# EVGP_Daugherboard_2.net
KiCad netlist of a schematic drawn in EAGLE
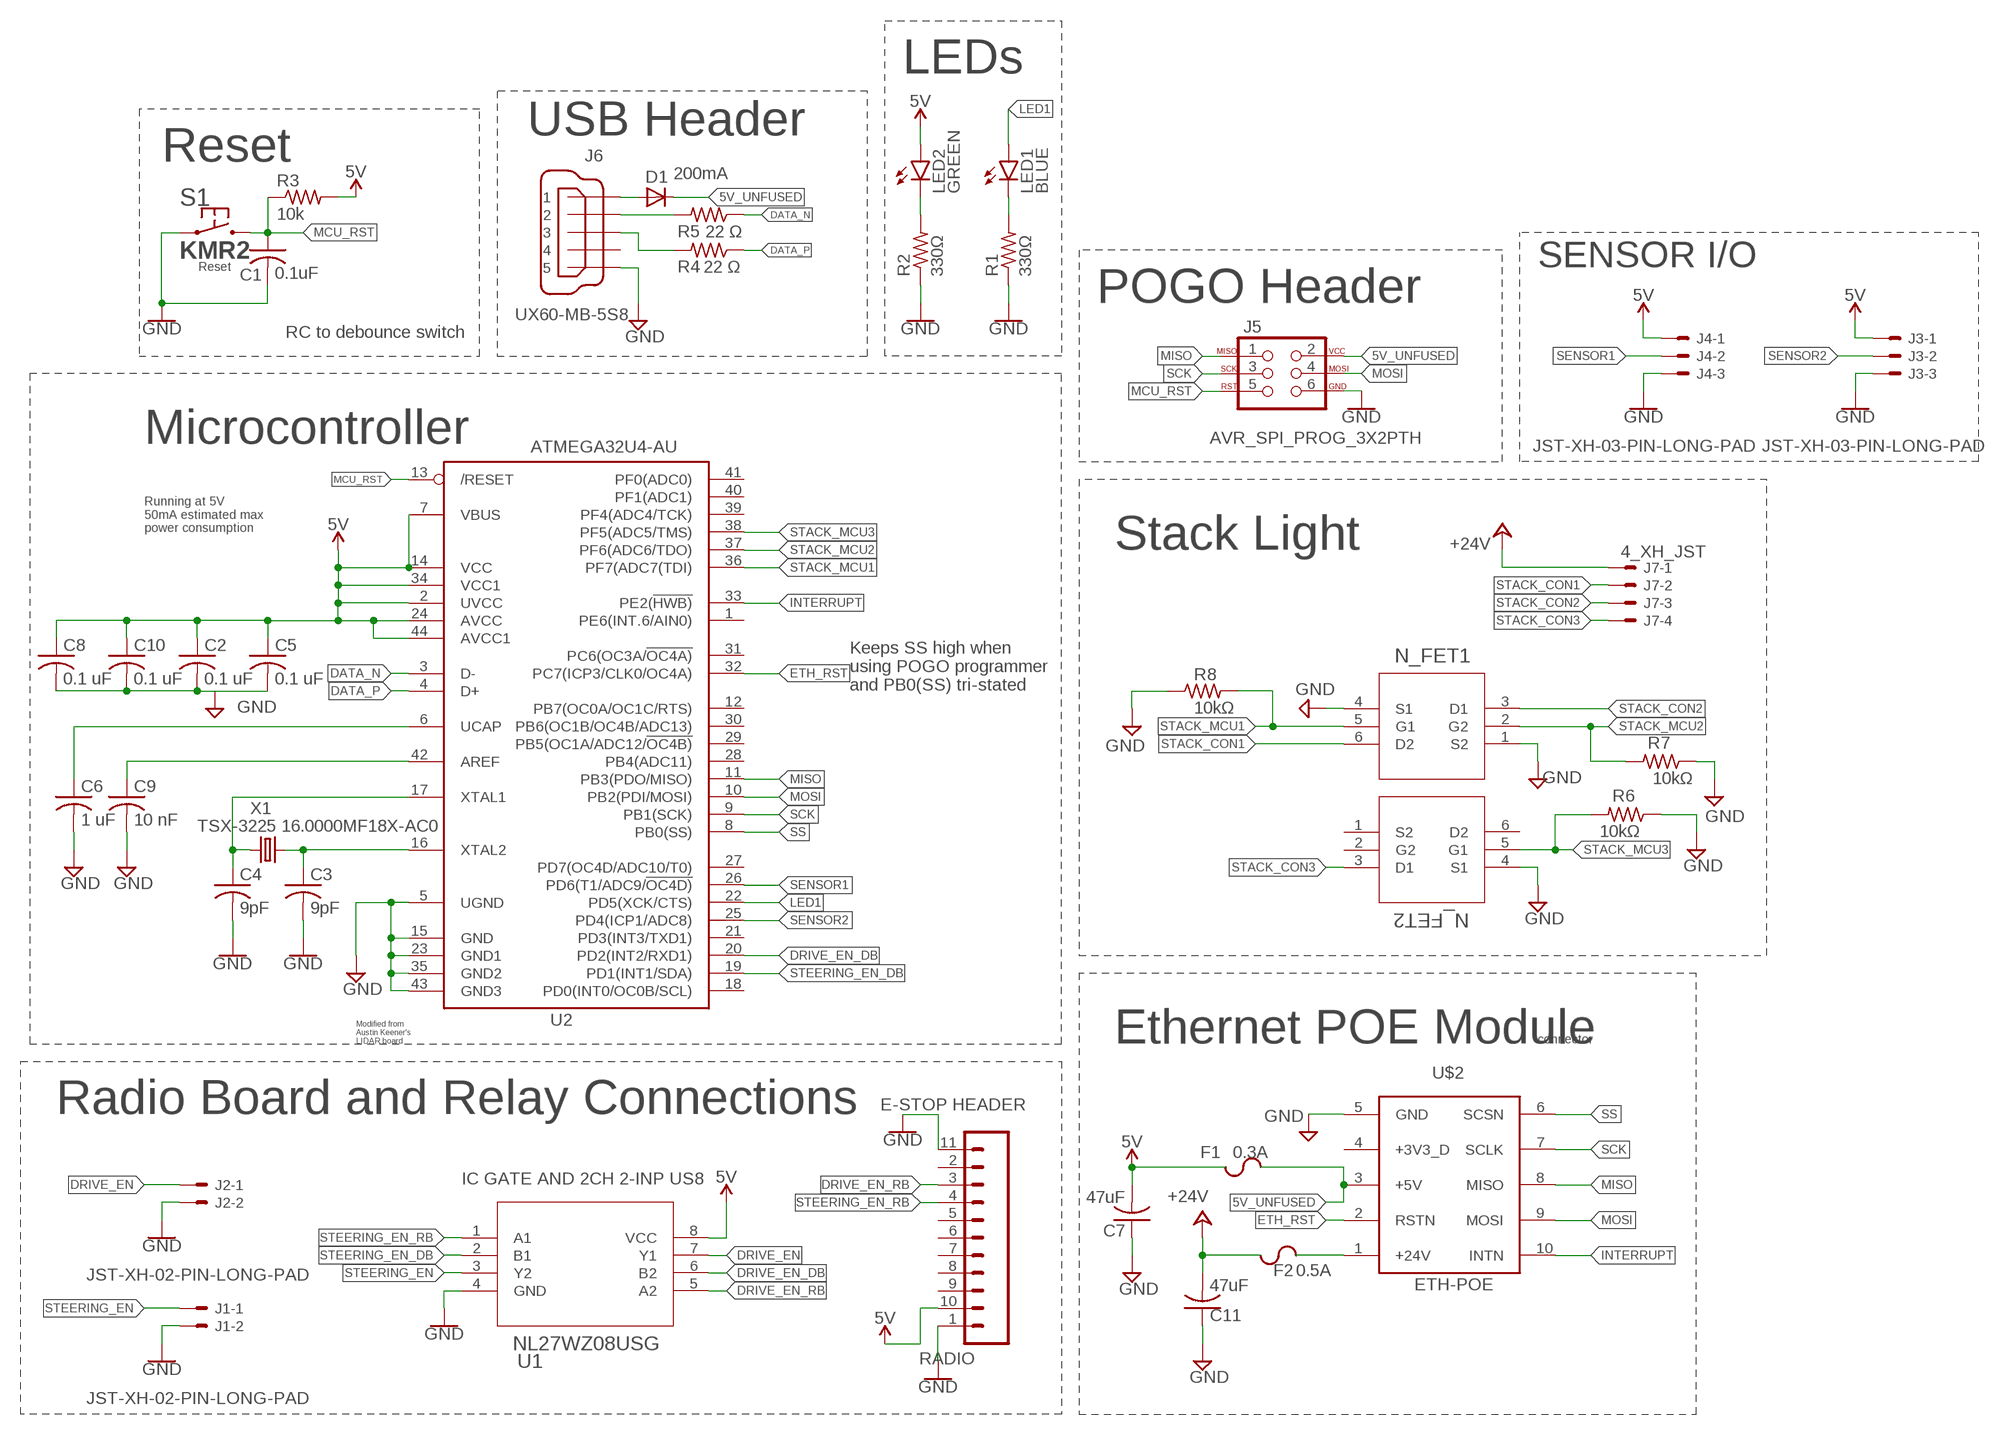
[diagram p0: schematic, sheet 1]

(export (version "E")
  (design (tool "Eeschema 10.0.6"))
  (components
    (comp (ref "C1")
      (value "0.1uF")
      (footprint "eagle-import:C0603")
      (libsource (lib "eagle-import") (part "C-USC0603"))
    )
    (comp (ref "C2")
      (value "0.1 uF")
      (footprint "eagle-import:C0603")
      (libsource (lib "eagle-import") (part "resistor_348_C-USC0603"))
    )
    (comp (ref "C3")
      (value "9pF")
      (footprint "eagle-import:C0603")
      (libsource (lib "eagle-import") (part "resistor_348_C-USC0603"))
    )
    (comp (ref "C4")
      (value "9pF")
      (footprint "eagle-import:C0603")
      (libsource (lib "eagle-import") (part "resistor_348_C-USC0603"))
    )
    (comp (ref "C5")
      (value "0.1 uF")
      (footprint "eagle-import:C0603")
      (libsource (lib "eagle-import") (part "resistor_348_C-USC0603"))
    )
    (comp (ref "C6")
      (value "1 uF")
      (footprint "eagle-import:C0603")
      (libsource (lib "eagle-import") (part "resistor_348_C-USC0603"))
    )
    (comp (ref "C7")
      (value "47uF")
      (footprint "eagle-import:C1206")
      (libsource (lib "eagle-import") (part "C-USC1206"))
    )
    (comp (ref "C8")
      (value "0.1 uF")
      (footprint "eagle-import:C0603")
      (libsource (lib "eagle-import") (part "resistor_348_C-USC0603"))
    )
    (comp (ref "C9")
      (value "10 nF")
      (footprint "eagle-import:C0603")
      (libsource (lib "eagle-import") (part "resistor_348_C-USC0603"))
    )
    (comp (ref "C10")
      (value "0.1 uF")
      (footprint "eagle-import:C0603")
      (libsource (lib "eagle-import") (part "resistor_348_C-USC0603"))
    )
    (comp (ref "C11")
      (value "47uF")
      (footprint "eagle-import:C1206")
      (libsource (lib "eagle-import") (part "C-USC1206"))
    )
    (comp (ref "D1")
      (value "200mA")
      (footprint "eagle-import:SOD323-R")
      (libsource (lib "eagle-import") (part "DIODE-SOD323-R"))
    )
    (comp (ref "F1")
      (value "0.3A")
      (footprint "eagle-import:F1206")
      (libsource (lib "eagle-import") (part "CHIP_FUSE1206"))
    )
    (comp (ref "F2")
      (value "0.5A")
      (footprint "eagle-import:F1206")
      (libsource (lib "eagle-import") (part "CHIP_FUSE1206"))
    )
    (comp (ref "J1")
      (value "JST-XH-02-PIN-LONG-PAD")
      (footprint "eagle-import:JST-XH-02-PACKAGE-LONG-PAD")
      (libsource (lib "eagle-import") (part "JST-XH-02-PIN-LONG-PAD"))
    )
    (comp (ref "J2")
      (value "JST-XH-02-PIN-LONG-PAD")
      (footprint "eagle-import:JST-XH-02-PACKAGE-LONG-PAD")
      (libsource (lib "eagle-import") (part "JST-XH-02-PIN-LONG-PAD"))
    )
    (comp (ref "J3")
      (value "JST-XH-03-PIN-LONG-PAD")
      (footprint "eagle-import:JST-XH-03-PACKAGE-LONG-PAD")
      (libsource (lib "eagle-import") (part "JST-XH-03-PIN-LONG-PAD"))
    )
    (comp (ref "J4")
      (value "JST-XH-03-PIN-LONG-PAD")
      (footprint "eagle-import:JST-XH-03-PACKAGE-LONG-PAD")
      (libsource (lib "eagle-import") (part "JST-XH-03-PIN-LONG-PAD"))
    )
    (comp (ref "J5")
      (value "AVR_SPI_PROG_3X2PTH")
      (footprint "eagle-import:2X3")
      (libsource (lib "eagle-import") (part "AVR_SPI_PROG_3X2PTH"))
    )
    (comp (ref "J6")
      (value "UX60-MB-5S8")
      (footprint "eagle-import:UX60-MB-5S8")
      (libsource (lib "eagle-import") (part "UX60-MB-5S?8"))
    )
    (comp (ref "J7")
      (value "4_XH_JST")
      (footprint "eagle-import:JST-XH-04-PACKAGE-LONG-PAD")
      (libsource (lib "eagle-import") (part "JST-XH-04-PIN-LONG-PAD"))
    )
    (comp (ref "LED1")
      (value "BLUE")
      (footprint "eagle-import:CHIP-LED0603")
      (libsource (lib "eagle-import") (part "LEDCHIP-LED0603"))
    )
    (comp (ref "LED2")
      (value "GREEN")
      (footprint "eagle-import:CHIP-LED0603")
      (libsource (lib "eagle-import") (part "LEDCHIP-LED0603"))
    )
    (comp (ref "Q1")
      (value "N_FET2")
      (footprint "eagle-import:SOT-363")
      (fields (field (name "MANUFACTURER_PART_NUMBER") "BSS84DW7F"))
      (libsource (lib "eagle-import") (part "BSS84DW-7-F"))
    )
    (comp (ref "Q2")
      (value "N_FET1")
      (footprint "eagle-import:SOT-363")
      (fields (field (name "MANUFACTURER_PART_NUMBER") "BSS84DW7F"))
      (libsource (lib "eagle-import") (part "BSS84DW-7-F"))
    )
    (comp (ref "R1")
      (value "330Ω")
      (footprint "eagle-import:R0603")
      (libsource (lib "eagle-import") (part "R-US_R0603"))
    )
    (comp (ref "R2")
      (value "330Ω")
      (footprint "eagle-import:R0603")
      (libsource (lib "eagle-import") (part "R-US_R0603"))
    )
    (comp (ref "R3")
      (value "10k")
      (footprint "eagle-import:R0603")
      (libsource (lib "eagle-import") (part "R-US_R0603"))
    )
    (comp (ref "R4")
      (value "22 Ω")
      (footprint "eagle-import:R0603")
      (libsource (lib "eagle-import") (part "R-US_R0603"))
    )
    (comp (ref "R5")
      (value "22 Ω")
      (footprint "eagle-import:R0603")
      (libsource (lib "eagle-import") (part "R-US_R0603"))
    )
    (comp (ref "R6")
      (value "10kΩ")
      (footprint "eagle-import:R0603")
      (libsource (lib "eagle-import") (part "R-US_R0603"))
    )
    (comp (ref "R7")
      (value "10kΩ")
      (footprint "eagle-import:R0603")
      (libsource (lib "eagle-import") (part "R-US_R0603"))
    )
    (comp (ref "R8")
      (value "10kΩ")
      (footprint "eagle-import:R0603")
      (libsource (lib "eagle-import") (part "R-US_R0603"))
    )
    (comp (ref "RADIO")
      (value "E-STOP HEADER")
      (footprint "eagle-import:RADIO_V1.3")
      (libsource (lib "eagle-import") (part "ESTOP_RADIO"))
    )
    (comp (ref "S1")
      (value "KMR2")
      (footprint "eagle-import:KMR2")
      (fields (field (name "FUNCTION") "Reset"))
      (libsource (lib "eagle-import") (part "KMR2"))
    )
    (comp (ref "U$2")
      (value "ETH-POE")
      (footprint "eagle-import:HDRVR10W64P4000X254_2X5_1016X508X254B")
      (libsource (lib "eagle-import") (part "ETH-POE"))
    )
    (comp (ref "U1")
      (value "NL27WZ08USG")
      (footprint "eagle-import:US8_2P40X2P10")
      (libsource (lib "eagle-import") (part "NL27WZ08USG"))
    )
    (comp (ref "U2")
      (value "ATMEGA32U4-AU")
      (footprint "eagle-import:TQFP44")
      (libsource (lib "eagle-import") (part "ATMEGA32U4-AU"))
    )
    (comp (ref "X1")
      (value "TSX-3225 16.0000MF18X-AC0")
      (footprint "eagle-import:XTAL-3.2X2.5")
      (libsource (lib "eagle-import") (part "XTAL-3.2X2.5"))
    )
  )
  (nets
    (net (code "1") (name "+24V") (class "Default")
      (node (ref "C11") (pin "2") (pinfunction "2_2") (pintype "passive"))
      (node (ref "F2") (pin "1") (pinfunction "1_1") (pintype "bidirectional"))
      (node (ref "J7") (pin "1") (pinfunction "S_1") (pintype "passive"))
    )
    (net (code "2") (name "5V") (class "Default")
      (node (ref "C10") (pin "1") (pinfunction "1_1") (pintype "passive"))
      (node (ref "C2") (pin "1") (pinfunction "1_1") (pintype "passive"))
      (node (ref "C5") (pin "1") (pinfunction "1_1") (pintype "passive"))
      (node (ref "C7") (pin "2") (pinfunction "2_2") (pintype "passive"))
      (node (ref "C8") (pin "1") (pinfunction "1_1") (pintype "passive"))
      (node (ref "F1") (pin "1") (pinfunction "1_1") (pintype "bidirectional"))
      (node (ref "J3") (pin "1") (pinfunction "S_1") (pintype "passive"))
      (node (ref "J4") (pin "1") (pinfunction "S_1") (pintype "passive"))
      (node (ref "LED2") (pin "A") (pinfunction "A_A") (pintype "passive"))
      (node (ref "R3") (pin "2") (pinfunction "2_2") (pintype "passive"))
      (node (ref "RADIO") (pin "10") (pinfunction "5V_10") (pintype "passive"))
      (node (ref "U1") (pin "8") (pinfunction "VCC_8") (pintype "power_in"))
      (node (ref "U2") (pin "14") (pinfunction "VCC_14") (pintype "bidirectional"))
      (node (ref "U2") (pin "2") (pinfunction "UVCC_2") (pintype "bidirectional"))
      (node (ref "U2") (pin "24") (pinfunction "AVCC_24") (pintype "bidirectional"))
      (node (ref "U2") (pin "34") (pinfunction "VCC1_34") (pintype "bidirectional"))
      (node (ref "U2") (pin "44") (pinfunction "AVCC1_44") (pintype "bidirectional"))
      (node (ref "U2") (pin "7") (pinfunction "VBUS_7") (pintype "bidirectional"))
    )
    (net (code "3") (name "5V_UNFUSED") (class "Default")
      (node (ref "D1") (pin "C") (pinfunction "C_C") (pintype "passive"))
      (node (ref "F1") (pin "2") (pinfunction "2_2") (pintype "bidirectional"))
      (node (ref "J5") (pin "2") (pinfunction "2_2") (pintype "passive"))
      (node (ref "U$2") (pin "3") (pinfunction "+5V_3") (pintype "bidirectional"))
    )
    (net (code "4") (name "DATA_N") (class "Default")
      (node (ref "R5") (pin "1") (pinfunction "1_1") (pintype "passive"))
      (node (ref "U2") (pin "3") (pinfunction "D-_3") (pintype "bidirectional"))
    )
    (net (code "5") (name "DATA_P") (class "Default")
      (node (ref "R4") (pin "1") (pinfunction "1_1") (pintype "passive"))
      (node (ref "U2") (pin "4") (pinfunction "D+_4") (pintype "bidirectional"))
    )
    (net (code "6") (name "DRIVE_EN") (class "Default")
      (node (ref "J2") (pin "1") (pinfunction "S_1") (pintype "passive"))
      (node (ref "U1") (pin "7") (pinfunction "Y1_7") (pintype "output"))
    )
    (net (code "7") (name "DRIVE_EN_DB") (class "Default")
      (node (ref "U1") (pin "6") (pinfunction "B2_6") (pintype "input"))
      (node (ref "U2") (pin "20") (pinfunction "PD2(INT2/RXD1)_20") (pintype "bidirectional"))
    )
    (net (code "8") (name "DRIVE_EN_RB") (class "Default")
      (node (ref "RADIO") (pin "3") (pinfunction "D1_3") (pintype "passive"))
      (node (ref "U1") (pin "5") (pinfunction "A2_5") (pintype "input"))
    )
    (net (code "9") (name "ETH_RST") (class "Default")
      (node (ref "U$2") (pin "2") (pinfunction "RSTN_2") (pintype "bidirectional"))
      (node (ref "U2") (pin "32") (pinfunction "PC7(ICP3/CLK0/OC4A)_32") (pintype "bidirectional"))
    )
    (net (code "10") (name "GND") (class "Default")
      (node (ref "C1") (pin "2") (pinfunction "2_2") (pintype "passive"))
      (node (ref "C10") (pin "2") (pinfunction "2_2") (pintype "passive"))
      (node (ref "C11") (pin "1") (pinfunction "1_1") (pintype "passive"))
      (node (ref "C2") (pin "2") (pinfunction "2_2") (pintype "passive"))
      (node (ref "C3") (pin "2") (pinfunction "2_2") (pintype "passive"))
      (node (ref "C4") (pin "2") (pinfunction "2_2") (pintype "passive"))
      (node (ref "C5") (pin "2") (pinfunction "2_2") (pintype "passive"))
      (node (ref "C6") (pin "2") (pinfunction "2_2") (pintype "passive"))
      (node (ref "C7") (pin "1") (pinfunction "1_1") (pintype "passive"))
      (node (ref "C8") (pin "2") (pinfunction "2_2") (pintype "passive"))
      (node (ref "C9") (pin "2") (pinfunction "2_2") (pintype "passive"))
      (node (ref "J1") (pin "2") (pinfunction "S_2") (pintype "passive"))
      (node (ref "J2") (pin "2") (pinfunction "S_2") (pintype "passive"))
      (node (ref "J3") (pin "3") (pinfunction "S_3") (pintype "passive"))
      (node (ref "J4") (pin "3") (pinfunction "S_3") (pintype "passive"))
      (node (ref "J5") (pin "6") (pinfunction "6_6") (pintype "passive"))
      (node (ref "J6") (pin "5") (pinfunction "5_5") (pintype "passive"))
      (node (ref "Q1") (pin "4") (pinfunction "S1_4") (pintype "passive"))
      (node (ref "Q2") (pin "1") (pinfunction "S2_1") (pintype "passive"))
      (node (ref "Q2") (pin "4") (pinfunction "S1_4") (pintype "passive"))
      (node (ref "R1") (pin "1") (pinfunction "1_1") (pintype "passive"))
      (node (ref "R2") (pin "1") (pinfunction "1_1") (pintype "passive"))
      (node (ref "R6") (pin "1") (pinfunction "1_1") (pintype "passive"))
      (node (ref "R7") (pin "1") (pinfunction "1_1") (pintype "passive"))
      (node (ref "R8") (pin "1") (pinfunction "1_1") (pintype "passive"))
      (node (ref "RADIO") (pin "1") (pinfunction "GND_1") (pintype "passive"))
      (node (ref "RADIO") (pin "11") (pinfunction "GND_11") (pintype "passive"))
      (node (ref "S1") (pin "1.1") (pinfunction "1_1.1") (pintype "passive"))
      (node (ref "S1") (pin "1.2") (pinfunction "1_1.2") (pintype "passive"))
      (node (ref "U$2") (pin "5") (pinfunction "GND_5") (pintype "bidirectional"))
      (node (ref "U1") (pin "4") (pinfunction "GND_4") (pintype "power_in"))
      (node (ref "U2") (pin "15") (pinfunction "GND_15") (pintype "bidirectional"))
      (node (ref "U2") (pin "23") (pinfunction "GND1_23") (pintype "bidirectional"))
      (node (ref "U2") (pin "35") (pinfunction "GND2_35") (pintype "bidirectional"))
      (node (ref "U2") (pin "43") (pinfunction "GND3_43") (pintype "bidirectional"))
      (node (ref "U2") (pin "5") (pinfunction "UGND_5") (pintype "bidirectional"))
    )
    (net (code "11") (name "INTERRUPT") (class "Default")
      (node (ref "U$2") (pin "10") (pinfunction "INTN_10") (pintype "bidirectional"))
      (node (ref "U2") (pin "33") (pinfunction "PE2(~{HWB})_33") (pintype "bidirectional"))
    )
    (net (code "12") (name "LED1") (class "Default")
      (node (ref "LED1") (pin "A") (pinfunction "A_A") (pintype "passive"))
      (node (ref "U2") (pin "22") (pinfunction "PD5(XCK/CTS)_22") (pintype "bidirectional"))
    )
    (net (code "13") (name "MCU_RST") (class "Default")
      (node (ref "C1") (pin "1") (pinfunction "1_1") (pintype "passive"))
      (node (ref "J5") (pin "5") (pinfunction "5_5") (pintype "passive"))
      (node (ref "R3") (pin "1") (pinfunction "1_1") (pintype "passive"))
      (node (ref "S1") (pin "2.1") (pinfunction "2_2.1") (pintype "passive"))
      (node (ref "S1") (pin "2.2") (pinfunction "2_2.2") (pintype "passive"))
      (node (ref "U2") (pin "13") (pinfunction "/RESET_13") (pintype "bidirectional"))
    )
    (net (code "14") (name "MISO") (class "Default")
      (node (ref "J5") (pin "1") (pinfunction "1_1") (pintype "passive"))
      (node (ref "U$2") (pin "8") (pinfunction "MISO_8") (pintype "bidirectional"))
      (node (ref "U2") (pin "11") (pinfunction "PB3(PDO/MISO)_11") (pintype "bidirectional"))
    )
    (net (code "15") (name "MOSI") (class "Default")
      (node (ref "J5") (pin "4") (pinfunction "4_4") (pintype "passive"))
      (node (ref "U$2") (pin "9") (pinfunction "MOSI_9") (pintype "bidirectional"))
      (node (ref "U2") (pin "10") (pinfunction "PB2(PDI/MOSI)_10") (pintype "bidirectional"))
    )
    (net (code "16") (name "Net-(D1-PadA)") (class "Default")
      (node (ref "D1") (pin "A") (pinfunction "A_A") (pintype "passive"))
      (node (ref "J6") (pin "1") (pinfunction "1_1") (pintype "passive"))
    )
    (net (code "17") (name "Net-(J6-Pad2)") (class "Default")
      (node (ref "J6") (pin "2") (pinfunction "2_2") (pintype "passive"))
      (node (ref "R5") (pin "2") (pinfunction "2_2") (pintype "passive"))
    )
    (net (code "18") (name "Net-(J6-Pad3)") (class "Default")
      (node (ref "J6") (pin "3") (pinfunction "3_3") (pintype "passive"))
      (node (ref "R4") (pin "2") (pinfunction "2_2") (pintype "passive"))
    )
    (net (code "19") (name "Net-(LED1-PadC)") (class "Default")
      (node (ref "LED1") (pin "C") (pinfunction "C_C") (pintype "passive"))
      (node (ref "R1") (pin "2") (pinfunction "2_2") (pintype "passive"))
    )
    (net (code "20") (name "Net-(LED2-PadC)") (class "Default")
      (node (ref "LED2") (pin "C") (pinfunction "C_C") (pintype "passive"))
      (node (ref "R2") (pin "2") (pinfunction "2_2") (pintype "passive"))
    )
    (net (code "21") (name "Net-(U$2-+24V)") (class "Default")
      (node (ref "F2") (pin "2") (pinfunction "2_2") (pintype "bidirectional"))
      (node (ref "U$2") (pin "1") (pinfunction "+24V_1") (pintype "bidirectional"))
    )
    (net (code "22") (name "Net-(U2-AREF)") (class "Default")
      (node (ref "C9") (pin "1") (pinfunction "1_1") (pintype "passive"))
      (node (ref "U2") (pin "42") (pinfunction "AREF_42") (pintype "bidirectional"))
    )
    (net (code "23") (name "Net-(U2-UCAP)") (class "Default")
      (node (ref "C6") (pin "1") (pinfunction "1_1") (pintype "passive"))
      (node (ref "U2") (pin "6") (pinfunction "UCAP_6") (pintype "bidirectional"))
    )
    (net (code "24") (name "Net-(U2-XTAL1)") (class "Default")
      (node (ref "C4") (pin "1") (pinfunction "1_1") (pintype "passive"))
      (node (ref "U2") (pin "17") (pinfunction "XTAL1_17") (pintype "bidirectional"))
      (node (ref "X1") (pin "1") (pinfunction "1_1") (pintype "passive"))
    )
    (net (code "25") (name "Net-(U2-XTAL2)") (class "Default")
      (node (ref "C3") (pin "1") (pinfunction "1_1") (pintype "passive"))
      (node (ref "U2") (pin "16") (pinfunction "XTAL2_16") (pintype "bidirectional"))
      (node (ref "X1") (pin "3") (pinfunction "2_3") (pintype "passive"))
    )
    (net (code "26") (name "SCK") (class "Default")
      (node (ref "J5") (pin "3") (pinfunction "3_3") (pintype "passive"))
      (node (ref "U$2") (pin "7") (pinfunction "SCLK_7") (pintype "bidirectional"))
      (node (ref "U2") (pin "9") (pinfunction "PB1(SCK)_9") (pintype "bidirectional"))
    )
    (net (code "27") (name "SENSOR1") (class "Default")
      (node (ref "J4") (pin "2") (pinfunction "S_2") (pintype "passive"))
      (node (ref "U2") (pin "26") (pinfunction "PD6(T1/ADC9/~{OC4D})_26") (pintype "bidirectional"))
    )
    (net (code "28") (name "SENSOR2") (class "Default")
      (node (ref "J3") (pin "2") (pinfunction "S_2") (pintype "passive"))
      (node (ref "U2") (pin "25") (pinfunction "PD4(ICP1/ADC8)_25") (pintype "bidirectional"))
    )
    (net (code "29") (name "SS") (class "Default")
      (node (ref "U$2") (pin "6") (pinfunction "SCSN_6") (pintype "bidirectional"))
      (node (ref "U2") (pin "8") (pinfunction "PB0(SS)_8") (pintype "bidirectional"))
    )
    (net (code "30") (name "STACK_CON1") (class "Default")
      (node (ref "J7") (pin "2") (pinfunction "S_2") (pintype "passive"))
      (node (ref "Q2") (pin "6") (pinfunction "D2_6") (pintype "passive"))
    )
    (net (code "31") (name "STACK_CON2") (class "Default")
      (node (ref "J7") (pin "3") (pinfunction "S_3") (pintype "passive"))
      (node (ref "Q2") (pin "3") (pinfunction "D1_3") (pintype "passive"))
    )
    (net (code "32") (name "STACK_CON3") (class "Default")
      (node (ref "J7") (pin "4") (pinfunction "S_4") (pintype "passive"))
      (node (ref "Q1") (pin "3") (pinfunction "D1_3") (pintype "passive"))
    )
    (net (code "33") (name "STACK_MCU1") (class "Default")
      (node (ref "Q2") (pin "5") (pinfunction "G1_5") (pintype "passive"))
      (node (ref "R8") (pin "2") (pinfunction "2_2") (pintype "passive"))
      (node (ref "U2") (pin "36") (pinfunction "PF7(ADC7(TDI)_36") (pintype "bidirectional"))
    )
    (net (code "34") (name "STACK_MCU2") (class "Default")
      (node (ref "Q2") (pin "2") (pinfunction "G2_2") (pintype "passive"))
      (node (ref "R7") (pin "2") (pinfunction "2_2") (pintype "passive"))
      (node (ref "U2") (pin "37") (pinfunction "PF6(ADC6/TDO)_37") (pintype "bidirectional"))
    )
    (net (code "35") (name "STACK_MCU3") (class "Default")
      (node (ref "Q1") (pin "5") (pinfunction "G1_5") (pintype "passive"))
      (node (ref "R6") (pin "2") (pinfunction "2_2") (pintype "passive"))
      (node (ref "U2") (pin "38") (pinfunction "PF5(ADC5/TMS)_38") (pintype "bidirectional"))
    )
    (net (code "36") (name "STEERING_EN") (class "Default")
      (node (ref "J1") (pin "1") (pinfunction "S_1") (pintype "passive"))
      (node (ref "U1") (pin "3") (pinfunction "Y2_3") (pintype "output"))
    )
    (net (code "37") (name "STEERING_EN_DB") (class "Default")
      (node (ref "U1") (pin "2") (pinfunction "B1_2") (pintype "input"))
      (node (ref "U2") (pin "19") (pinfunction "PD1(INT1/SDA)_19") (pintype "bidirectional"))
    )
    (net (code "38") (name "STEERING_EN_RB") (class "Default")
      (node (ref "RADIO") (pin "4") (pinfunction "D2_4") (pintype "passive"))
      (node (ref "U1") (pin "1") (pinfunction "A1_1") (pintype "input"))
    )
    (net (code "39") (name "unconnected-(J6-Pad4)") (class "Default")
      (node (ref "J6") (pin "4") (pinfunction "4_4") (pintype "passive"))
    )
    (net (code "40") (name "unconnected-(Q1-D2-Pad6)") (class "Default")
      (node (ref "Q1") (pin "6") (pinfunction "D2_6") (pintype "passive"))
    )
    (net (code "41") (name "unconnected-(Q1-G2-Pad2)") (class "Default")
      (node (ref "Q1") (pin "2") (pinfunction "G2_2") (pintype "passive"))
    )
    (net (code "42") (name "unconnected-(Q1-S2-Pad1)") (class "Default")
      (node (ref "Q1") (pin "1") (pinfunction "S2_1") (pintype "passive"))
    )
    (net (code "43") (name "unconnected-(RADIO-D3-Pad5)") (class "Default")
      (node (ref "RADIO") (pin "5") (pinfunction "D3_5") (pintype "passive"))
    )
    (net (code "44") (name "unconnected-(RADIO-D4-Pad6)") (class "Default")
      (node (ref "RADIO") (pin "6") (pinfunction "D4_6") (pintype "passive"))
    )
    (net (code "45") (name "unconnected-(RADIO-D5-Pad7)") (class "Default")
      (node (ref "RADIO") (pin "7") (pinfunction "D5_7") (pintype "passive"))
    )
    (net (code "46") (name "unconnected-(RADIO-D6-Pad8)") (class "Default")
      (node (ref "RADIO") (pin "8") (pinfunction "D6_8") (pintype "passive"))
    )
    (net (code "47") (name "unconnected-(RADIO-D7-Pad9)") (class "Default")
      (node (ref "RADIO") (pin "9") (pinfunction "D7_9") (pintype "passive"))
    )
    (net (code "48") (name "unconnected-(RADIO-RST-Pad2)") (class "Default")
      (node (ref "RADIO") (pin "2") (pinfunction "RST_2") (pintype "passive"))
    )
    (net (code "49") (name "unconnected-(U$2-+3V3_D-Pad4)") (class "Default")
      (node (ref "U$2") (pin "4") (pinfunction "+3V3_D_4") (pintype "bidirectional"))
    )
    (net (code "50") (name "unconnected-(U2-PB4(ADC11)-Pad28)") (class "Default")
      (node (ref "U2") (pin "28") (pinfunction "PB4(ADC11)_28") (pintype "bidirectional"))
    )
    (net (code "51") (name "unconnected-(U2-PB5(OC1A{slash}ADC12{slash}~{OC4B})-Pad29)") (class "Default")
      (node (ref "U2") (pin "29") (pinfunction "PB5(OC1A/ADC12/~{OC4B})_29") (pintype "bidirectional"))
    )
    (net (code "52") (name "unconnected-(U2-PB6(OC1B{slash}OC4B{slash}ADC13)-Pad30)") (class "Default")
      (node (ref "U2") (pin "30") (pinfunction "PB6(OC1B/OC4B/ADC13)_30") (pintype "bidirectional"))
    )
    (net (code "53") (name "unconnected-(U2-PB7(OC0A{slash}OC1C{slash}RTS)-Pad12)") (class "Default")
      (node (ref "U2") (pin "12") (pinfunction "PB7(OC0A/OC1C/RTS)_12") (pintype "bidirectional"))
    )
    (net (code "54") (name "unconnected-(U2-PC6(OC3A{slash}~{OC4A})-Pad31)") (class "Default")
      (node (ref "U2") (pin "31") (pinfunction "PC6(OC3A/~{OC4A})_31") (pintype "bidirectional"))
    )
    (net (code "55") (name "unconnected-(U2-PD0(INT0{slash}OC0B{slash}SCL)-Pad18)") (class "Default")
      (node (ref "U2") (pin "18") (pinfunction "PD0(INT0/OC0B/SCL)_18") (pintype "bidirectional"))
    )
    (net (code "56") (name "unconnected-(U2-PD3(INT3{slash}TXD1)-Pad21)") (class "Default")
      (node (ref "U2") (pin "21") (pinfunction "PD3(INT3/TXD1)_21") (pintype "bidirectional"))
    )
    (net (code "57") (name "unconnected-(U2-PD7(OC4D{slash}ADC10{slash}T0)-Pad27)") (class "Default")
      (node (ref "U2") (pin "27") (pinfunction "PD7(OC4D/ADC10/T0)_27") (pintype "bidirectional"))
    )
    (net (code "58") (name "unconnected-(U2-PE6(INT.6{slash}AIN0)-Pad1)") (class "Default")
      (node (ref "U2") (pin "1") (pinfunction "PE6(INT.6/AIN0)_1") (pintype "bidirectional"))
    )
    (net (code "59") (name "unconnected-(U2-PF0(ADC0)-Pad41)") (class "Default")
      (node (ref "U2") (pin "41") (pinfunction "PF0(ADC0)_41") (pintype "bidirectional"))
    )
    (net (code "60") (name "unconnected-(U2-PF1(ADC1)-Pad40)") (class "Default")
      (node (ref "U2") (pin "40") (pinfunction "PF1(ADC1)_40") (pintype "bidirectional"))
    )
    (net (code "61") (name "unconnected-(U2-PF4(ADC4{slash}TCK)-Pad39)") (class "Default")
      (node (ref "U2") (pin "39") (pinfunction "PF4(ADC4/TCK)_39") (pintype "bidirectional"))
    )
  )
)
